# UI-LEDs.net
KiCad netlist of a schematic drawn in Altium Designer
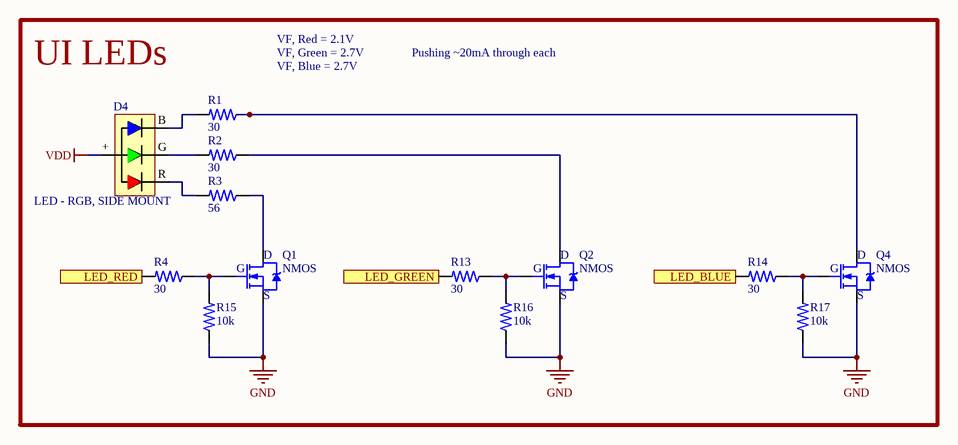
[diagram p0: UI-LEDs.SchDoc]

(export (version "E")
  (design (tool "Eeschema 10.0.6"))
  (components
    (comp (ref "D4")
      (value "LED - RGB, SIDE MOUNT")
      (footprint "PressurePulse:FM-3510RGBA-SG")
      (fields (field (name "MFR") "Foshan NationStar Optoelectronics"))
      (libsource (lib "PressurePulse") (part "LED - RGB, SIDE MOUNT"))
    )
    (comp (ref "Q1")
      (value "NMOS")
      (footprint "PressurePulse:SOT-23")
      (description "100V 1.6A 1.3W 220mΩ@10V,1.6A N Channel SOT-23  MOSFETs ROHS")
      (fields (field (name "MFR") "Infineon"))
      (libsource (lib "PressurePulse") (part "NMOS"))
    )
    (comp (ref "Q2")
      (value "NMOS")
      (footprint "PressurePulse:SOT-23")
      (description "100V 1.6A 1.3W 220mΩ@10V,1.6A N Channel SOT-23  MOSFETs ROHS")
      (fields (field (name "MFR") "Infineon"))
      (libsource (lib "PressurePulse") (part "NMOS"))
    )
    (comp (ref "Q4")
      (value "NMOS")
      (footprint "PressurePulse:SOT-23")
      (description "100V 1.6A 1.3W 220mΩ@10V,1.6A N Channel SOT-23  MOSFETs ROHS")
      (fields (field (name "MFR") "Infineon"))
      (libsource (lib "PressurePulse") (part "NMOS"))
    )
    (comp (ref "R1")
      (value "30")
      (footprint "PressurePulse:0402R")
      (description "Resistor")
      (fields (field (name "Comment") "RES"))
      (libsource (lib "PressurePulse") (part "RES"))
    )
    (comp (ref "R2")
      (value "30")
      (footprint "PressurePulse:0402R")
      (description "Resistor")
      (fields (field (name "Comment") "RES"))
      (libsource (lib "PressurePulse") (part "RES"))
    )
    (comp (ref "R3")
      (value "56")
      (footprint "PressurePulse:0402R")
      (description "Resistor")
      (fields (field (name "Comment") "RES"))
      (libsource (lib "PressurePulse") (part "RES"))
    )
    (comp (ref "R4")
      (value "30")
      (footprint "PressurePulse:0402R")
      (description "Resistor")
      (fields (field (name "Comment") "RES"))
      (libsource (lib "PressurePulse") (part "RES"))
    )
    (comp (ref "R13")
      (value "30")
      (footprint "PressurePulse:0402R")
      (description "Resistor")
      (fields (field (name "Comment") "RES"))
      (libsource (lib "PressurePulse") (part "RES"))
    )
    (comp (ref "R14")
      (value "30")
      (footprint "PressurePulse:0402R")
      (description "Resistor")
      (fields (field (name "Comment") "RES"))
      (libsource (lib "PressurePulse") (part "RES"))
    )
    (comp (ref "R15")
      (value "10k")
      (footprint "PressurePulse:0402R")
      (description "Resistor")
      (fields (field (name "Comment") "RES"))
      (libsource (lib "PressurePulse") (part "RES"))
    )
    (comp (ref "R16")
      (value "10k")
      (footprint "PressurePulse:0402R")
      (description "Resistor")
      (fields (field (name "Comment") "RES"))
      (libsource (lib "PressurePulse") (part "RES"))
    )
    (comp (ref "R17")
      (value "10k")
      (footprint "PressurePulse:0402R")
      (description "Resistor")
      (fields (field (name "Comment") "RES"))
      (libsource (lib "PressurePulse") (part "RES"))
    )
  )
  (nets
    (net (code "1") (name "/LED_BLUE") (class "Default")
      (node (ref "R14") (pin "2") (pinfunction "2_2") (pintype "passive"))
    )
    (net (code "2") (name "/LED_GREEN") (class "Default")
      (node (ref "R13") (pin "2") (pinfunction "2_2") (pintype "passive"))
    )
    (net (code "3") (name "/LED_RED") (class "Default")
      (node (ref "R4") (pin "2") (pinfunction "2_2") (pintype "passive"))
    )
    (net (code "4") (name "GND") (class "Default")
      (node (ref "Q1") (pin "S") (pinfunction "S_S") (pintype "passive"))
      (node (ref "Q2") (pin "S") (pinfunction "S_S") (pintype "passive"))
      (node (ref "Q4") (pin "S") (pinfunction "S_S") (pintype "passive"))
      (node (ref "R15") (pin "1") (pinfunction "1_1") (pintype "passive"))
      (node (ref "R16") (pin "1") (pinfunction "1_1") (pintype "passive"))
      (node (ref "R17") (pin "1") (pinfunction "1_1") (pintype "passive"))
    )
    (net (code "5") (name "Net-(D4-PadB)") (class "Default")
      (node (ref "D4") (pin "B") (pinfunction "B_B") (pintype "passive"))
      (node (ref "R1") (pin "2") (pinfunction "2_2") (pintype "passive"))
    )
    (net (code "6") (name "Net-(D4-PadG)") (class "Default")
      (node (ref "D4") (pin "G") (pinfunction "G_G") (pintype "passive"))
      (node (ref "R2") (pin "2") (pinfunction "2_2") (pintype "passive"))
    )
    (net (code "7") (name "Net-(D4-PadR)") (class "Default")
      (node (ref "D4") (pin "R") (pinfunction "R_R") (pintype "passive"))
      (node (ref "R3") (pin "2") (pinfunction "2_2") (pintype "passive"))
    )
    (net (code "8") (name "Net-(Q1-PadD)") (class "Default")
      (node (ref "Q1") (pin "D") (pinfunction "D_D") (pintype "passive"))
      (node (ref "R3") (pin "1") (pinfunction "1_1") (pintype "passive"))
    )
    (net (code "9") (name "Net-(Q1-PadG)") (class "Default")
      (node (ref "Q1") (pin "G") (pinfunction "G_G") (pintype "passive"))
      (node (ref "R15") (pin "2") (pinfunction "2_2") (pintype "passive"))
      (node (ref "R4") (pin "1") (pinfunction "1_1") (pintype "passive"))
    )
    (net (code "10") (name "Net-(Q2-PadD)") (class "Default")
      (node (ref "Q2") (pin "D") (pinfunction "D_D") (pintype "passive"))
      (node (ref "R2") (pin "1") (pinfunction "1_1") (pintype "passive"))
    )
    (net (code "11") (name "Net-(Q2-PadG)") (class "Default")
      (node (ref "Q2") (pin "G") (pinfunction "G_G") (pintype "passive"))
      (node (ref "R13") (pin "1") (pinfunction "1_1") (pintype "passive"))
      (node (ref "R16") (pin "2") (pinfunction "2_2") (pintype "passive"))
    )
    (net (code "12") (name "Net-(Q4-PadD)") (class "Default")
      (node (ref "Q4") (pin "D") (pinfunction "D_D") (pintype "passive"))
      (node (ref "R1") (pin "1") (pinfunction "1_1") (pintype "passive"))
    )
    (net (code "13") (name "Net-(Q4-PadG)") (class "Default")
      (node (ref "Q4") (pin "G") (pinfunction "G_G") (pintype "passive"))
      (node (ref "R14") (pin "1") (pinfunction "1_1") (pintype "passive"))
      (node (ref "R17") (pin "2") (pinfunction "2_2") (pintype "passive"))
    )
    (net (code "14") (name "VDD") (class "Default")
      (node (ref "D4") (pin "+") (pinfunction "+_+") (pintype "passive"))
    )
  )
)
